# Tilt-Power.net
KiCad netlist of a schematic drawn in Altium Designer
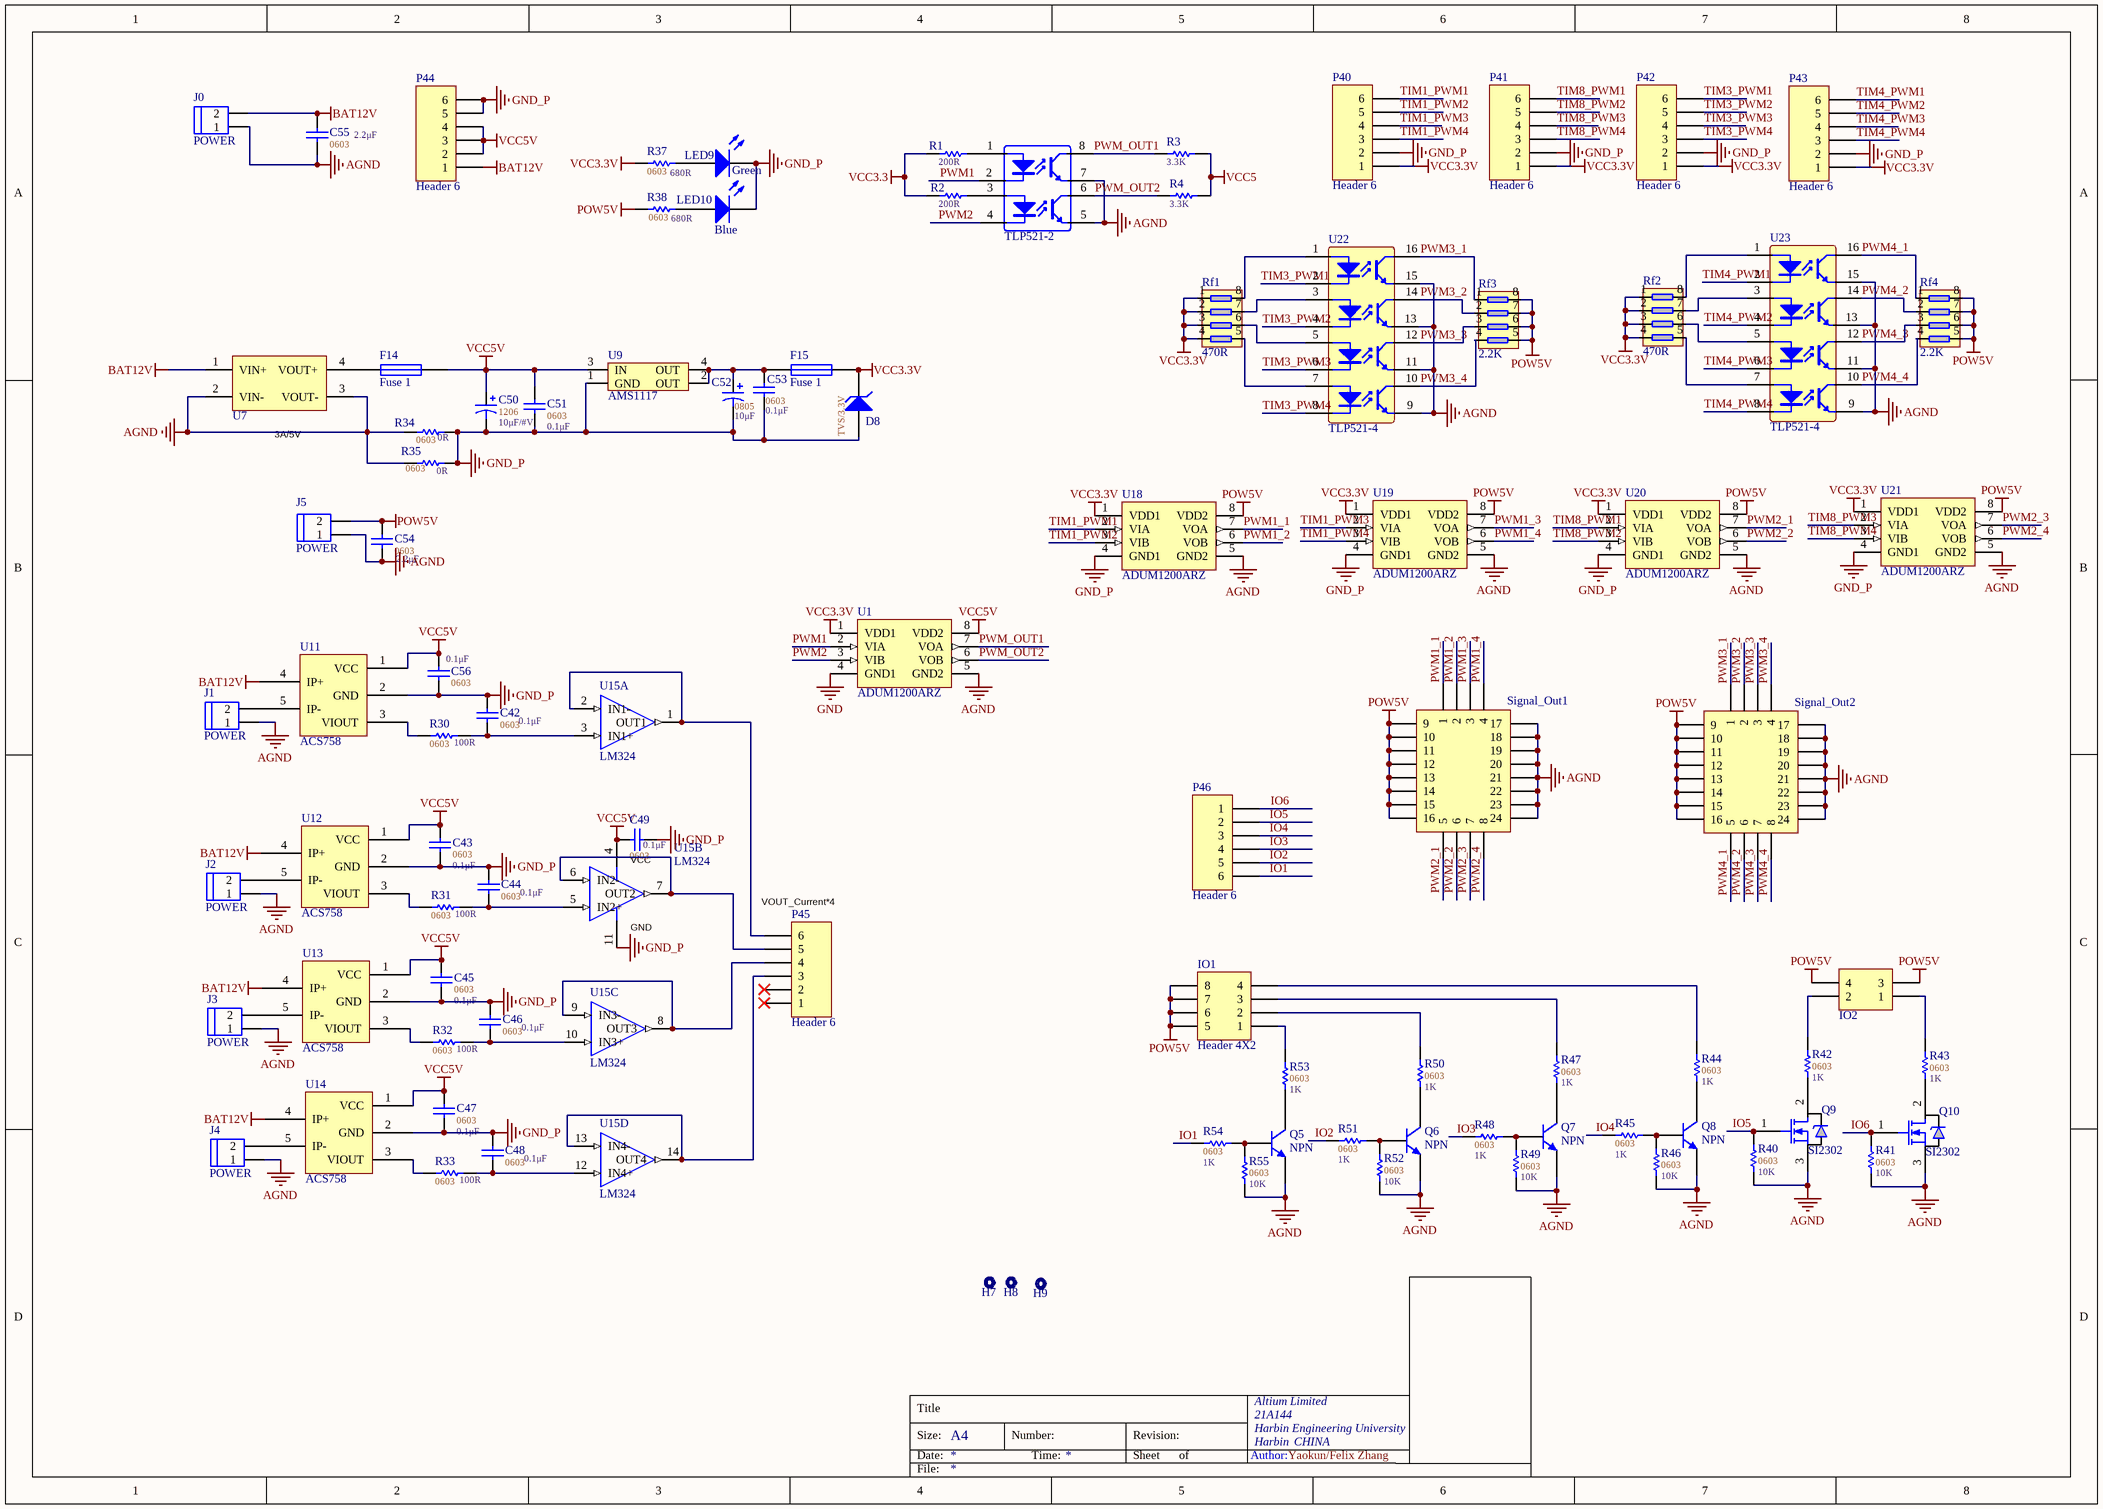
[diagram p0: Tilt-Power.SchDoc]

(export (version "E")
  (design (tool "Eeschema 10.0.6"))
  (components
    (comp (ref "*") (value "TLP521-2") (libsource (lib "Belong_to_Kongkong") (part "TLP521-2")))
    (comp (ref "C42")
      (value "0.1μF")
      (footprint "CAP_0603_16*08")
      (description "Capacitor")
      (fields (field (name "PACKAGEREFERENCE") "0603") (field (name "Comment") "0603"))
      (libsource (lib "Belong_to_Kongkong") (part "Cap"))
    )
    (comp (ref "C43")
      (value "0.1μF")
      (footprint "CAP_0603_16*08")
      (description "Capacitor")
      (fields (field (name "PACKAGEREFERENCE") "0603") (field (name "Comment") "0603"))
      (libsource (lib "Belong_to_Kongkong") (part "Cap"))
    )
    (comp (ref "C44")
      (value "0.1μF")
      (footprint "CAP_0603_16*08")
      (description "Capacitor")
      (fields (field (name "PACKAGEREFERENCE") "0603") (field (name "Comment") "0603"))
      (libsource (lib "Belong_to_Kongkong") (part "Cap"))
    )
    (comp (ref "C45")
      (value "0.1μF")
      (footprint "CAP_0603_16*08")
      (description "Capacitor")
      (fields (field (name "PACKAGEREFERENCE") "0603") (field (name "Comment") "0603"))
      (libsource (lib "Belong_to_Kongkong") (part "Cap"))
    )
    (comp (ref "C46")
      (value "0.1μF")
      (footprint "CAP_0603_16*08")
      (description "Capacitor")
      (fields (field (name "PACKAGEREFERENCE") "0603") (field (name "Comment") "0603"))
      (libsource (lib "Belong_to_Kongkong") (part "Cap"))
    )
    (comp (ref "C47")
      (value "0.1μF")
      (footprint "CAP_0603_16*08")
      (description "Capacitor")
      (fields (field (name "PACKAGEREFERENCE") "0603") (field (name "Comment") "0603"))
      (libsource (lib "Belong_to_Kongkong") (part "Cap"))
    )
    (comp (ref "C48")
      (value "0.1μF")
      (footprint "CAP_0603_16*08")
      (description "Capacitor")
      (fields (field (name "PACKAGEREFERENCE") "0603") (field (name "Comment") "0603"))
      (libsource (lib "Belong_to_Kongkong") (part "Cap"))
    )
    (comp (ref "C49")
      (value "0.1μF")
      (footprint "CAP_0603_16*08")
      (description "Capacitor")
      (fields (field (name "PACKAGEREFERENCE") "0603") (field (name "Comment") "0603"))
      (libsource (lib "Belong_to_Kongkong") (part "Cap"))
    )
    (comp (ref "C50")
      (value "10μF/#V")
      (footprint "CAP_1206")
      (description "Polarized Capacitor (Axial)")
      (fields (field (name "PACKAGEREFERENCE") "1206") (field (name "Comment") "Polar"))
      (libsource (lib "Belong_to_Kongkong") (part "Cap Pol"))
    )
    (comp (ref "C51")
      (value "0.1μF")
      (footprint "CAP_0603_16*08")
      (description "Capacitor")
      (fields (field (name "PACKAGEREFERENCE") "0603") (field (name "Comment") "0603"))
      (libsource (lib "Belong_to_Kongkong") (part "Cap"))
    )
    (comp (ref "C52")
      (value "10μF")
      (footprint "CAP_0805_20*12")
      (description "Polarized Capacitor (Axial)")
      (fields (field (name "PACKAGEREFERENCE") "0805") (field (name "Comment") "Polar"))
      (libsource (lib "Belong_to_Kongkong") (part "Cap Pol"))
    )
    (comp (ref "C53")
      (value "0.1μF")
      (footprint "CAP_0603_16*08")
      (description "Capacitor")
      (fields (field (name "PACKAGEREFERENCE") "0603") (field (name "Comment") "0603"))
      (libsource (lib "Belong_to_Kongkong") (part "Cap"))
    )
    (comp (ref "C54")
      (value "2.2μF")
      (footprint "CAP_0805_20*12")
      (description "Capacitor")
      (fields (field (name "PACKAGEREFERENCE") "0603") (field (name "Comment") "0603"))
      (libsource (lib "Belong_to_Kongkong") (part "Cap"))
    )
    (comp (ref "C55")
      (value "2.2μF")
      (footprint "CAP_0805_20*12")
      (description "Capacitor")
      (fields (field (name "PACKAGEREFERENCE") "0603") (field (name "Comment") "0603"))
      (libsource (lib "Belong_to_Kongkong") (part "Cap"))
    )
    (comp (ref "C56")
      (value "0.1μF")
      (footprint "CAP_0603_16*08")
      (description "Capacitor")
      (fields (field (name "PACKAGEREFERENCE") "0603") (field (name "Comment") "0603"))
      (libsource (lib "Belong_to_Kongkong") (part "Cap"))
    )
    (comp (ref "D8")
      (value "TVS/3.3V")
      (footprint "SOD523")
      (description "Zener Diode")
      (libsource (lib "Belong_to_Kongkong") (part "D Zener"))
    )
    (comp (ref "F14")
      (value "Fuse 1")
      (footprint "FUSE3.5*5.5")
      (description "Fuse")
      (libsource (lib "Belong_to_Kongkong") (part "Fuse 1"))
    )
    (comp (ref "F15")
      (value "Fuse 1")
      (footprint "RES_0805_20*12")
      (description "Fuse")
      (libsource (lib "Belong_to_Kongkong") (part "Fuse 1"))
    )
    (comp (ref "H7") (value "pad") (footprint "PAD_M2") (libsource (lib "Belong_to_Kongkong") (part "pad")))
    (comp (ref "H8") (value "pad") (footprint "PAD_M2") (libsource (lib "Belong_to_Kongkong") (part "pad")))
    (comp (ref "H9") (value "pad") (footprint "PAD_M2") (libsource (lib "Belong_to_Kongkong") (part "pad")))
    (comp (ref "IO1")
      (value "Header 4X2")
      (footprint "HEADER2*4_PIN")
      (description "Header, 4-Pin, Dual row")
      (libsource (lib "Belong_to_Kongkong") (part "Header 4X2"))
    )
    (comp (ref "IO2")
      (value "Header 2X2")
      (footprint "HEADER2*2_PIN")
      (description "Header, 2-Pin, Dual row")
      (libsource (lib "Belong_to_Kongkong") (part "Header 2X2"))
    )
    (comp (ref "J0")
      (value "POWER")
      (footprint "POWER_PADS")
      (libsource (lib "Belong_to_Kongkong") (part "HEAD2"))
    )
    (comp (ref "J1")
      (value "POWER")
      (footprint "POWER_PADS")
      (libsource (lib "Belong_to_Kongkong") (part "HEAD2"))
    )
    (comp (ref "J2")
      (value "POWER")
      (footprint "POWER_PADS")
      (libsource (lib "Belong_to_Kongkong") (part "HEAD2"))
    )
    (comp (ref "J3")
      (value "POWER")
      (footprint "POWER_PADS")
      (libsource (lib "Belong_to_Kongkong") (part "HEAD2"))
    )
    (comp (ref "J4")
      (value "POWER")
      (footprint "POWER_PADS")
      (libsource (lib "Belong_to_Kongkong") (part "HEAD2"))
    )
    (comp (ref "J5")
      (value "POWER")
      (footprint "POWER_PADS")
      (libsource (lib "Belong_to_Kongkong") (part "HEAD2"))
    )
    (comp (ref "LED9")
      (value "Green")
      (footprint "LED0603")
      (description "Typical RED, GREEN, YELLOW, AMBER GaAs LED")
      (libsource (lib "Belong_to_Kongkong") (part "LED"))
    )
    (comp (ref "LED10")
      (value "Blue")
      (footprint "LED0603")
      (description "Typical RED, GREEN, YELLOW, AMBER GaAs LED")
      (libsource (lib "Belong_to_Kongkong") (part "LED"))
    )
    (comp (ref "P40")
      (value "Header 6")
      (footprint "Modolex_6P")
      (description "Header, 6-Pin")
      (libsource (lib "Belong_to_Kongkong") (part "Header 6"))
    )
    (comp (ref "P41")
      (value "Header 6")
      (footprint "Modolex_6P")
      (description "Header, 6-Pin")
      (libsource (lib "Belong_to_Kongkong") (part "Header 6"))
    )
    (comp (ref "P42")
      (value "Header 6")
      (footprint "Modolex_6P")
      (description "Header, 6-Pin")
      (libsource (lib "Belong_to_Kongkong") (part "Header 6"))
    )
    (comp (ref "P43")
      (value "Header 6")
      (footprint "Modolex_6P")
      (description "Header, 6-Pin")
      (libsource (lib "Belong_to_Kongkong") (part "Header 6"))
    )
    (comp (ref "P44")
      (value "Header 6")
      (footprint "Modolex_6P")
      (description "Header, 6-Pin")
      (libsource (lib "Belong_to_Kongkong") (part "Header 6"))
    )
    (comp (ref "P45")
      (value "Header 6")
      (footprint "Modolex_6P")
      (description "Header, 6-Pin")
      (libsource (lib "") (part "Header 6_2"))
    )
    (comp (ref "P46")
      (value "Header 6")
      (footprint "Modolex_6P")
      (description "Header, 6-Pin")
      (libsource (lib "") (part "Header 6_1"))
    )
    (comp (ref "Q5")
      (value "NPN")
      (footprint "SOT23_J3Y")
      (description "NPN Bipolar Transistor")
      (libsource (lib "Belong_to_Kongkong") (part "NPN"))
    )
    (comp (ref "Q6")
      (value "NPN")
      (footprint "SOT23_J3Y")
      (description "NPN Bipolar Transistor")
      (libsource (lib "Belong_to_Kongkong") (part "NPN"))
    )
    (comp (ref "Q7")
      (value "NPN")
      (footprint "SOT23_J3Y")
      (description "NPN Bipolar Transistor")
      (libsource (lib "Belong_to_Kongkong") (part "NPN"))
    )
    (comp (ref "Q8")
      (value "NPN")
      (footprint "SOT23_J3Y")
      (description "NPN Bipolar Transistor")
      (libsource (lib "Belong_to_Kongkong") (part "NPN"))
    )
    (comp (ref "Q9")
      (value "SI2302")
      (footprint "SOT-23_MOSN")
      (description "N-Channel MOSFET")
      (libsource (lib "Belong_to_Kongkong") (part "MOSFET-N"))
    )
    (comp (ref "Q10")
      (value "SI2302")
      (footprint "SOT-23_MOSN")
      (description "N-Channel MOSFET")
      (libsource (lib "Belong_to_Kongkong") (part "MOSFET-N"))
    )
    (comp (ref "R1")
      (value "200R")
      (footprint "RES_0402_10*06")
      (description "Resistor")
      (fields (field (name "Comment") "SMD"))
      (libsource (lib "Belong_to_Kongkong") (part "RES_SMD"))
    )
    (comp (ref "R2")
      (value "200R")
      (footprint "RES_0402_10*06")
      (description "Resistor")
      (fields (field (name "Comment") "SMD"))
      (libsource (lib "Belong_to_Kongkong") (part "RES_SMD"))
    )
    (comp (ref "R3")
      (value "3.3K")
      (footprint "RES_0402_10*06")
      (description "Resistor")
      (fields (field (name "Comment") "SMD"))
      (libsource (lib "Belong_to_Kongkong") (part "RES_SMD"))
    )
    (comp (ref "R4")
      (value "3.3K")
      (footprint "RES_0402_10*06")
      (description "Resistor")
      (fields (field (name "Comment") "SMD"))
      (libsource (lib "Belong_to_Kongkong") (part "RES_SMD"))
    )
    (comp (ref "R30")
      (value "100R")
      (footprint "RES_0603_16*08")
      (description "Resistor")
      (fields (field (name "PACKAGEREFERENCE") "0603") (field (name "Comment") "SMD"))
      (libsource (lib "Belong_to_Kongkong") (part "RES_SMD"))
    )
    (comp (ref "R31")
      (value "100R")
      (footprint "RES_0603_16*08")
      (description "Resistor")
      (fields (field (name "PACKAGEREFERENCE") "0603") (field (name "Comment") "SMD"))
      (libsource (lib "Belong_to_Kongkong") (part "RES_SMD"))
    )
    (comp (ref "R32")
      (value "100R")
      (footprint "RES_0603_16*08")
      (description "Resistor")
      (fields (field (name "PACKAGEREFERENCE") "0603") (field (name "Comment") "SMD"))
      (libsource (lib "Belong_to_Kongkong") (part "RES_SMD"))
    )
    (comp (ref "R33")
      (value "100R")
      (footprint "RES_0603_16*08")
      (description "Resistor")
      (fields (field (name "PACKAGEREFERENCE") "0603") (field (name "Comment") "SMD"))
      (libsource (lib "Belong_to_Kongkong") (part "RES_SMD"))
    )
    (comp (ref "R34")
      (value "0R")
      (footprint "RES_1206")
      (description "Resistor")
      (fields (field (name "PACKAGEREFERENCE") "0603") (field (name "Comment") "SMD"))
      (libsource (lib "Belong_to_Kongkong") (part "RES_SMD"))
    )
    (comp (ref "R35")
      (value "0R")
      (footprint "RES_1206")
      (description "Resistor")
      (fields (field (name "PACKAGEREFERENCE") "0603") (field (name "Comment") "SMD"))
      (libsource (lib "Belong_to_Kongkong") (part "RES_SMD"))
    )
    (comp (ref "R37")
      (value "680R")
      (footprint "RES_0603_16*08")
      (description "Resistor")
      (fields (field (name "PACKAGEREFERENCE") "0603") (field (name "Comment") "SMD"))
      (libsource (lib "Belong_to_Kongkong") (part "RES_SMD"))
    )
    (comp (ref "R38")
      (value "680R")
      (footprint "RES_0603_16*08")
      (description "Resistor")
      (fields (field (name "PACKAGEREFERENCE") "0603") (field (name "Comment") "SMD"))
      (libsource (lib "Belong_to_Kongkong") (part "RES_SMD"))
    )
    (comp (ref "R40")
      (value "10K")
      (footprint "RES_0603_16*08")
      (description "Resistor")
      (fields (field (name "PACKAGEREFERENCE") "0603") (field (name "Comment") "SMD"))
      (libsource (lib "Belong_to_Kongkong") (part "RES_SMD"))
    )
    (comp (ref "R41")
      (value "10K")
      (footprint "RES_0603_16*08")
      (description "Resistor")
      (fields (field (name "PACKAGEREFERENCE") "0603") (field (name "Comment") "SMD"))
      (libsource (lib "Belong_to_Kongkong") (part "RES_SMD"))
    )
    (comp (ref "R42")
      (value "1K")
      (footprint "RES_0603_16*08")
      (description "Resistor")
      (fields (field (name "PACKAGEREFERENCE") "0603") (field (name "Comment") "SMD"))
      (libsource (lib "Belong_to_Kongkong") (part "RES_SMD"))
    )
    (comp (ref "R43")
      (value "1K")
      (footprint "RES_0603_16*08")
      (description "Resistor")
      (fields (field (name "PACKAGEREFERENCE") "0603") (field (name "Comment") "SMD"))
      (libsource (lib "Belong_to_Kongkong") (part "RES_SMD"))
    )
    (comp (ref "R44")
      (value "1K")
      (footprint "RES_0603_16*08")
      (description "Resistor")
      (fields (field (name "PACKAGEREFERENCE") "0603") (field (name "Comment") "SMD"))
      (libsource (lib "Belong_to_Kongkong") (part "RES_SMD"))
    )
    (comp (ref "R45")
      (value "1K")
      (footprint "RES_0603_16*08")
      (description "Resistor")
      (fields (field (name "PACKAGEREFERENCE") "0603") (field (name "Comment") "SMD"))
      (libsource (lib "Belong_to_Kongkong") (part "RES_SMD"))
    )
    (comp (ref "R46")
      (value "10K")
      (footprint "RES_0603_16*08")
      (description "Resistor")
      (fields (field (name "PACKAGEREFERENCE") "0603") (field (name "Comment") "SMD"))
      (libsource (lib "Belong_to_Kongkong") (part "RES_SMD"))
    )
    (comp (ref "R47")
      (value "1K")
      (footprint "RES_0603_16*08")
      (description "Resistor")
      (fields (field (name "PACKAGEREFERENCE") "0603") (field (name "Comment") "SMD"))
      (libsource (lib "Belong_to_Kongkong") (part "RES_SMD"))
    )
    (comp (ref "R48")
      (value "1K")
      (footprint "RES_0603_16*08")
      (description "Resistor")
      (fields (field (name "PACKAGEREFERENCE") "0603") (field (name "Comment") "SMD"))
      (libsource (lib "Belong_to_Kongkong") (part "RES_SMD"))
    )
    (comp (ref "R49")
      (value "10K")
      (footprint "RES_0603_16*08")
      (description "Resistor")
      (fields (field (name "PACKAGEREFERENCE") "0603") (field (name "Comment") "SMD"))
      (libsource (lib "Belong_to_Kongkong") (part "RES_SMD"))
    )
    (comp (ref "R50")
      (value "1K")
      (footprint "RES_0603_16*08")
      (description "Resistor")
      (fields (field (name "PACKAGEREFERENCE") "0603") (field (name "Comment") "SMD"))
      (libsource (lib "Belong_to_Kongkong") (part "RES_SMD"))
    )
    (comp (ref "R51")
      (value "1K")
      (footprint "RES_0603_16*08")
      (description "Resistor")
      (fields (field (name "PACKAGEREFERENCE") "0603") (field (name "Comment") "SMD"))
      (libsource (lib "Belong_to_Kongkong") (part "RES_SMD"))
    )
    (comp (ref "R52")
      (value "10K")
      (footprint "RES_0603_16*08")
      (description "Resistor")
      (fields (field (name "PACKAGEREFERENCE") "0603") (field (name "Comment") "SMD"))
      (libsource (lib "Belong_to_Kongkong") (part "RES_SMD"))
    )
    (comp (ref "R53")
      (value "1K")
      (footprint "RES_0603_16*08")
      (description "Resistor")
      (fields (field (name "PACKAGEREFERENCE") "0603") (field (name "Comment") "SMD"))
      (libsource (lib "Belong_to_Kongkong") (part "RES_SMD"))
    )
    (comp (ref "R54")
      (value "1K")
      (footprint "RES_0603_16*08")
      (description "Resistor")
      (fields (field (name "PACKAGEREFERENCE") "0603") (field (name "Comment") "SMD"))
      (libsource (lib "Belong_to_Kongkong") (part "RES_SMD"))
    )
    (comp (ref "R55")
      (value "10K")
      (footprint "RES_0603_16*08")
      (description "Resistor")
      (fields (field (name "PACKAGEREFERENCE") "0603") (field (name "Comment") "SMD"))
      (libsource (lib "Belong_to_Kongkong") (part "RES_SMD"))
    )
    (comp (ref "Rf1")
      (value "470R")
      (footprint "RES_FOUR_0603")
      (libsource (lib "Belong_to_Kongkong") (part "RES_4P"))
    )
    (comp (ref "Rf2")
      (value "470R")
      (footprint "RES_FOUR_0603")
      (libsource (lib "Belong_to_Kongkong") (part "RES_4P"))
    )
    (comp (ref "Rf3")
      (value "2.2K")
      (footprint "RES_FOUR_0603")
      (libsource (lib "Belong_to_Kongkong") (part "RES_4P"))
    )
    (comp (ref "Rf4")
      (value "2.2K")
      (footprint "RES_FOUR_0603")
      (libsource (lib "Belong_to_Kongkong") (part "RES_4P"))
    )
    (comp (ref "Signal_Out1")
      (value "PWM")
      (footprint "HEADER3*8")
      (libsource (lib "Belong_to_Kongkong") (part "HEADER8*3"))
    )
    (comp (ref "Signal_Out2")
      (value "PWM")
      (footprint "HEADER3*8")
      (libsource (lib "Belong_to_Kongkong") (part "HEADER8*3"))
    )
    (comp (ref "U1")
      (value "ADUM1200ARZ")
      (footprint "SOIC-8")
      (description "ADUM1200")
      (libsource (lib "Belong_to_Kongkong") (part "ADUM1200ARZ"))
    )
    (comp (ref "U7")
      (value "Voltage_Trans_Moduel")
      (footprint "3A_Moduel")
      (libsource (lib "Belong_to_Kongkong") (part "Voltage_Trans_Moduel"))
    )
    (comp (ref "U9")
      (value "AMS1117")
      (footprint "SOT223_M")
      (libsource (lib "Belong_to_Kongkong") (part "AMS1117"))
    )
    (comp (ref "U11")
      (value "ACS758")
      (footprint "ACS758")
      (libsource (lib "Belong_to_Kongkong") (part "ACS758"))
    )
    (comp (ref "U12")
      (value "ACS758")
      (footprint "ACS758")
      (libsource (lib "Belong_to_Kongkong") (part "ACS758"))
    )
    (comp (ref "U13")
      (value "ACS758")
      (footprint "ACS758")
      (libsource (lib "Belong_to_Kongkong") (part "ACS758"))
    )
    (comp (ref "U14")
      (value "ACS758")
      (footprint "ACS758")
      (libsource (lib "Belong_to_Kongkong") (part "ACS758"))
    )
    (comp (ref "U15")
      (value "LM324")
      (footprint "SOP-14N")
      (libsource (lib "Belong_to_Kongkong") (part "LM324"))
    )
    (comp (ref "U18")
      (value "ADUM1200ARZ")
      (footprint "SOIC-8")
      (description "ADUM1200")
      (libsource (lib "Belong_to_Kongkong") (part "ADUM1200ARZ"))
    )
    (comp (ref "U19")
      (value "ADUM1200ARZ")
      (footprint "SOIC-8")
      (description "ADUM1200")
      (libsource (lib "Belong_to_Kongkong") (part "ADUM1200ARZ"))
    )
    (comp (ref "U20")
      (value "ADUM1200ARZ")
      (footprint "SOIC-8")
      (description "ADUM1200")
      (libsource (lib "Belong_to_Kongkong") (part "ADUM1200ARZ"))
    )
    (comp (ref "U21")
      (value "ADUM1200ARZ")
      (footprint "SOIC-8")
      (description "ADUM1200")
      (libsource (lib "Belong_to_Kongkong") (part "ADUM1200ARZ"))
    )
    (comp (ref "U22")
      (value "TLP521-4")
      (footprint "SOP16")
      (libsource (lib "Belong_to_Kongkong") (part "TLP521-4"))
    )
    (comp (ref "U23")
      (value "TLP521-4")
      (footprint "SOP16")
      (libsource (lib "Belong_to_Kongkong") (part "TLP521-4"))
    )
  )
  (nets
    (net (code "1") (name "/IO1") (class "Default")
      (node (ref "P46") (pin "6") (pinfunction "6_6") (pintype "passive"))
      (node (ref "R54") (pin "1") (pinfunction "1_1") (pintype "passive"))
    )
    (net (code "2") (name "/IO2") (class "Default")
      (node (ref "P46") (pin "5") (pinfunction "5_5") (pintype "passive"))
      (node (ref "R51") (pin "1") (pinfunction "1_1") (pintype "passive"))
    )
    (net (code "3") (name "/IO3") (class "Default")
      (node (ref "P46") (pin "4") (pinfunction "4_4") (pintype "passive"))
      (node (ref "R48") (pin "1") (pinfunction "1_1") (pintype "passive"))
    )
    (net (code "4") (name "/IO4") (class "Default")
      (node (ref "P46") (pin "3") (pinfunction "3_3") (pintype "passive"))
      (node (ref "R45") (pin "1") (pinfunction "1_1") (pintype "passive"))
    )
    (net (code "5") (name "/IO5") (class "Default")
      (node (ref "P46") (pin "2") (pinfunction "2_2") (pintype "passive"))
      (node (ref "Q9") (pin "1") (pinfunction "G_1") (pintype "passive"))
      (node (ref "R40") (pin "2") (pinfunction "2_2") (pintype "passive"))
    )
    (net (code "6") (name "/IO6") (class "Default")
      (node (ref "P46") (pin "1") (pinfunction "1_1") (pintype "passive"))
      (node (ref "Q10") (pin "1") (pinfunction "G_1") (pintype "passive"))
      (node (ref "R41") (pin "2") (pinfunction "2_2") (pintype "passive"))
    )
    (net (code "7") (name "/PWM1") (class "Default")
      (node (ref "*") (pin "2") (pinfunction "2_2") (pintype "power_in"))
      (node (ref "U1") (pin "2") (pinfunction "VIA_2") (pintype "input"))
    )
    (net (code "8") (name "/PWM1_1") (class "Default")
      (node (ref "Signal_Out1") (pin "1") (pinfunction "1_1") (pintype "passive"))
      (node (ref "U18") (pin "7") (pinfunction "VOA_7") (pintype "output"))
    )
    (net (code "9") (name "/PWM1_2") (class "Default")
      (node (ref "Signal_Out1") (pin "2") (pinfunction "2_2") (pintype "passive"))
      (node (ref "U18") (pin "6") (pinfunction "VOB_6") (pintype "output"))
    )
    (net (code "10") (name "/PWM1_3") (class "Default")
      (node (ref "Signal_Out1") (pin "3") (pinfunction "3_3") (pintype "passive"))
      (node (ref "U19") (pin "7") (pinfunction "VOA_7") (pintype "output"))
    )
    (net (code "11") (name "/PWM1_4") (class "Default")
      (node (ref "Signal_Out1") (pin "4") (pinfunction "4_4") (pintype "passive"))
      (node (ref "U19") (pin "6") (pinfunction "VOB_6") (pintype "output"))
    )
    (net (code "12") (name "/PWM2") (class "Default")
      (node (ref "*") (pin "4") (pinfunction "4_4") (pintype "power_in"))
      (node (ref "U1") (pin "3") (pinfunction "VIB_3") (pintype "input"))
    )
    (net (code "13") (name "/PWM2_1") (class "Default")
      (node (ref "Signal_Out1") (pin "5") (pinfunction "5_5") (pintype "passive"))
      (node (ref "U20") (pin "7") (pinfunction "VOA_7") (pintype "output"))
    )
    (net (code "14") (name "/PWM2_2") (class "Default")
      (node (ref "Signal_Out1") (pin "6") (pinfunction "6_6") (pintype "passive"))
      (node (ref "U20") (pin "6") (pinfunction "VOB_6") (pintype "output"))
    )
    (net (code "15") (name "/PWM2_3") (class "Default")
      (node (ref "Signal_Out1") (pin "7") (pinfunction "7_7") (pintype "passive"))
      (node (ref "U21") (pin "7") (pinfunction "VOA_7") (pintype "output"))
    )
    (net (code "16") (name "/PWM2_4") (class "Default")
      (node (ref "Signal_Out1") (pin "8") (pinfunction "8_8") (pintype "passive"))
      (node (ref "U21") (pin "6") (pinfunction "VOB_6") (pintype "output"))
    )
    (net (code "17") (name "/PWM3_1") (class "Default")
      (node (ref "Rf3") (pin "1") (pinfunction "1_1") (pintype "passive"))
      (node (ref "Signal_Out2") (pin "1") (pinfunction "1_1") (pintype "passive"))
      (node (ref "U22") (pin "16") (pinfunction "16_16") (pintype "power_in"))
    )
    (net (code "18") (name "/PWM3_2") (class "Default")
      (node (ref "Rf3") (pin "2") (pinfunction "2_2") (pintype "passive"))
      (node (ref "Signal_Out2") (pin "2") (pinfunction "2_2") (pintype "passive"))
      (node (ref "U22") (pin "14") (pinfunction "14_14") (pintype "power_in"))
    )
    (net (code "19") (name "/PWM3_3") (class "Default")
      (node (ref "Rf3") (pin "3") (pinfunction "3_3") (pintype "passive"))
      (node (ref "Signal_Out2") (pin "3") (pinfunction "3_3") (pintype "passive"))
      (node (ref "U22") (pin "12") (pinfunction "12_12") (pintype "power_in"))
    )
    (net (code "20") (name "/PWM3_4") (class "Default")
      (node (ref "Rf3") (pin "4") (pinfunction "4_4") (pintype "passive"))
      (node (ref "Signal_Out2") (pin "4") (pinfunction "4_4") (pintype "passive"))
      (node (ref "U22") (pin "10") (pinfunction "10_10") (pintype "power_in"))
    )
    (net (code "21") (name "/PWM4_1") (class "Default")
      (node (ref "Rf4") (pin "1") (pinfunction "1_1") (pintype "passive"))
      (node (ref "Signal_Out2") (pin "5") (pinfunction "5_5") (pintype "passive"))
      (node (ref "U23") (pin "16") (pinfunction "16_16") (pintype "power_in"))
    )
    (net (code "22") (name "/PWM4_2") (class "Default")
      (node (ref "Rf4") (pin "2") (pinfunction "2_2") (pintype "passive"))
      (node (ref "Signal_Out2") (pin "6") (pinfunction "6_6") (pintype "passive"))
      (node (ref "U23") (pin "14") (pinfunction "14_14") (pintype "power_in"))
    )
    (net (code "23") (name "/PWM4_3") (class "Default")
      (node (ref "Rf4") (pin "3") (pinfunction "3_3") (pintype "passive"))
      (node (ref "Signal_Out2") (pin "7") (pinfunction "7_7") (pintype "passive"))
      (node (ref "U23") (pin "12") (pinfunction "12_12") (pintype "power_in"))
    )
    (net (code "24") (name "/PWM4_4") (class "Default")
      (node (ref "Rf4") (pin "4") (pinfunction "4_4") (pintype "passive"))
      (node (ref "Signal_Out2") (pin "8") (pinfunction "8_8") (pintype "passive"))
      (node (ref "U23") (pin "10") (pinfunction "10_10") (pintype "power_in"))
    )
    (net (code "25") (name "/PWM_OUT1") (class "Default")
      (node (ref "*") (pin "8") (pinfunction "8_8") (pintype "power_in"))
      (node (ref "R3") (pin "1") (pinfunction "1_1") (pintype "passive"))
      (node (ref "U1") (pin "7") (pinfunction "VOA_7") (pintype "output"))
    )
    (net (code "26") (name "/PWM_OUT2") (class "Default")
      (node (ref "*") (pin "6") (pinfunction "6_6") (pintype "power_in"))
      (node (ref "R4") (pin "1") (pinfunction "1_1") (pintype "passive"))
      (node (ref "U1") (pin "6") (pinfunction "VOB_6") (pintype "output"))
    )
    (net (code "27") (name "/TIM1_PWM1") (class "Default")
      (node (ref "P40") (pin "6") (pinfunction "6_6") (pintype "passive"))
      (node (ref "U18") (pin "2") (pinfunction "VIA_2") (pintype "input"))
    )
    (net (code "28") (name "/TIM1_PWM2") (class "Default")
      (node (ref "P40") (pin "5") (pinfunction "5_5") (pintype "passive"))
      (node (ref "U18") (pin "3") (pinfunction "VIB_3") (pintype "input"))
    )
    (net (code "29") (name "/TIM1_PWM3") (class "Default")
      (node (ref "P40") (pin "4") (pinfunction "4_4") (pintype "passive"))
      (node (ref "U19") (pin "2") (pinfunction "VIA_2") (pintype "input"))
    )
    (net (code "30") (name "/TIM1_PWM4") (class "Default")
      (node (ref "P40") (pin "3") (pinfunction "3_3") (pintype "passive"))
      (node (ref "U19") (pin "3") (pinfunction "VIB_3") (pintype "input"))
    )
    (net (code "31") (name "/TIM3_PWM1") (class "Default")
      (node (ref "P42") (pin "6") (pinfunction "6_6") (pintype "passive"))
      (node (ref "U22") (pin "2") (pinfunction "2_2") (pintype "power_in"))
    )
    (net (code "32") (name "/TIM3_PWM2") (class "Default")
      (node (ref "P42") (pin "5") (pinfunction "5_5") (pintype "passive"))
      (node (ref "U22") (pin "4") (pinfunction "4_4") (pintype "power_in"))
    )
    (net (code "33") (name "/TIM3_PWM3") (class "Default")
      (node (ref "P42") (pin "4") (pinfunction "4_4") (pintype "passive"))
      (node (ref "U22") (pin "6") (pinfunction "6_6") (pintype "power_in"))
    )
    (net (code "34") (name "/TIM3_PWM4") (class "Default")
      (node (ref "P42") (pin "3") (pinfunction "3_3") (pintype "passive"))
      (node (ref "U22") (pin "8") (pinfunction "8_8") (pintype "power_in"))
    )
    (net (code "35") (name "/TIM4_PWM1") (class "Default")
      (node (ref "P43") (pin "6") (pinfunction "6_6") (pintype "passive"))
      (node (ref "U23") (pin "2") (pinfunction "2_2") (pintype "power_in"))
    )
    (net (code "36") (name "/TIM4_PWM2") (class "Default")
      (node (ref "P43") (pin "5") (pinfunction "5_5") (pintype "passive"))
      (node (ref "U23") (pin "4") (pinfunction "4_4") (pintype "power_in"))
    )
    (net (code "37") (name "/TIM4_PWM3") (class "Default")
      (node (ref "P43") (pin "4") (pinfunction "4_4") (pintype "passive"))
      (node (ref "U23") (pin "6") (pinfunction "6_6") (pintype "power_in"))
    )
    (net (code "38") (name "/TIM4_PWM4") (class "Default")
      (node (ref "P43") (pin "3") (pinfunction "3_3") (pintype "passive"))
      (node (ref "U23") (pin "8") (pinfunction "8_8") (pintype "power_in"))
    )
    (net (code "39") (name "/TIM8_PWM1") (class "Default")
      (node (ref "P41") (pin "6") (pinfunction "6_6") (pintype "passive"))
      (node (ref "U20") (pin "2") (pinfunction "VIA_2") (pintype "input"))
    )
    (net (code "40") (name "/TIM8_PWM2") (class "Default")
      (node (ref "P41") (pin "5") (pinfunction "5_5") (pintype "passive"))
      (node (ref "U20") (pin "3") (pinfunction "VIB_3") (pintype "input"))
    )
    (net (code "41") (name "/TIM8_PWM3") (class "Default")
      (node (ref "P41") (pin "4") (pinfunction "4_4") (pintype "passive"))
      (node (ref "U21") (pin "2") (pinfunction "VIA_2") (pintype "input"))
    )
    (net (code "42") (name "/TIM8_PWM4") (class "Default")
      (node (ref "P41") (pin "3") (pinfunction "3_3") (pintype "passive"))
      (node (ref "U21") (pin "3") (pinfunction "VIB_3") (pintype "input"))
    )
    (net (code "43") (name "AGND") (class "Default")
      (node (ref "*") (pin "5") (pinfunction "5_5") (pintype "power_in"))
      (node (ref "*") (pin "7") (pinfunction "7_7") (pintype "power_in"))
      (node (ref "C54") (pin "1") (pinfunction "1_1") (pintype "passive"))
      (node (ref "C55") (pin "1") (pinfunction "1_1") (pintype "passive"))
      (node (ref "J0") (pin "1") (pinfunction "1_1") (pintype "passive"))
      (node (ref "J1") (pin "1") (pinfunction "1_1") (pintype "passive"))
      (node (ref "J2") (pin "1") (pinfunction "1_1") (pintype "passive"))
      (node (ref "J3") (pin "1") (pinfunction "1_1") (pintype "passive"))
      (node (ref "J4") (pin "1") (pinfunction "1_1") (pintype "passive"))
      (node (ref "J5") (pin "1") (pinfunction "1_1") (pintype "passive"))
      (node (ref "Q10") (pin "3") (pinfunction "S_3") (pintype "passive"))
      (node (ref "Q5") (pin "3") (pinfunction "E_3") (pintype "passive"))
      (node (ref "Q6") (pin "3") (pinfunction "E_3") (pintype "passive"))
      (node (ref "Q7") (pin "3") (pinfunction "E_3") (pintype "passive"))
      (node (ref "Q8") (pin "3") (pinfunction "E_3") (pintype "passive"))
      (node (ref "Q9") (pin "3") (pinfunction "S_3") (pintype "passive"))
      (node (ref "R34") (pin "1") (pinfunction "1_1") (pintype "passive"))
      (node (ref "R35") (pin "1") (pinfunction "1_1") (pintype "passive"))
      (node (ref "R40") (pin "1") (pinfunction "1_1") (pintype "passive"))
      (node (ref "R41") (pin "1") (pinfunction "1_1") (pintype "passive"))
      (node (ref "R46") (pin "1") (pinfunction "1_1") (pintype "passive"))
      (node (ref "R49") (pin "1") (pinfunction "1_1") (pintype "passive"))
      (node (ref "R52") (pin "1") (pinfunction "1_1") (pintype "passive"))
      (node (ref "R55") (pin "1") (pinfunction "1_1") (pintype "passive"))
      (node (ref "Signal_Out1") (pin "17") (pinfunction "17_17") (pintype "passive"))
      (node (ref "Signal_Out1") (pin "18") (pinfunction "18_18") (pintype "passive"))
      (node (ref "Signal_Out1") (pin "19") (pinfunction "19_19") (pintype "passive"))
      (node (ref "Signal_Out1") (pin "20") (pinfunction "20_20") (pintype "passive"))
      (node (ref "Signal_Out1") (pin "21") (pinfunction "21_21") (pintype "passive"))
      (node (ref "Signal_Out1") (pin "22") (pinfunction "22_22") (pintype "passive"))
      (node (ref "Signal_Out1") (pin "23") (pinfunction "23_23") (pintype "passive"))
      (node (ref "Signal_Out1") (pin "24") (pinfunction "24_24") (pintype "passive"))
      (node (ref "Signal_Out2") (pin "17") (pinfunction "17_17") (pintype "passive"))
      (node (ref "Signal_Out2") (pin "18") (pinfunction "18_18") (pintype "passive"))
      (node (ref "Signal_Out2") (pin "19") (pinfunction "19_19") (pintype "passive"))
      (node (ref "Signal_Out2") (pin "20") (pinfunction "20_20") (pintype "passive"))
      (node (ref "Signal_Out2") (pin "21") (pinfunction "21_21") (pintype "passive"))
      (node (ref "Signal_Out2") (pin "22") (pinfunction "22_22") (pintype "passive"))
      (node (ref "Signal_Out2") (pin "23") (pinfunction "23_23") (pintype "passive"))
      (node (ref "Signal_Out2") (pin "24") (pinfunction "24_24") (pintype "passive"))
      (node (ref "U1") (pin "5") (pinfunction "GND2_5") (pintype "power_in"))
      (node (ref "U18") (pin "5") (pinfunction "GND2_5") (pintype "power_in"))
      (node (ref "U19") (pin "5") (pinfunction "GND2_5") (pintype "power_in"))
      (node (ref "U20") (pin "5") (pinfunction "GND2_5") (pintype "power_in"))
      (node (ref "U21") (pin "5") (pinfunction "GND2_5") (pintype "power_in"))
      (node (ref "U22") (pin "11") (pinfunction "11_11") (pintype "power_in"))
      (node (ref "U22") (pin "13") (pinfunction "13_13") (pintype "power_in"))
      (node (ref "U22") (pin "15") (pinfunction "15_15") (pintype "power_in"))
      (node (ref "U22") (pin "9") (pinfunction "9_9") (pintype "power_in"))
      (node (ref "U23") (pin "11") (pinfunction "11_11") (pintype "power_in"))
      (node (ref "U23") (pin "13") (pinfunction "13_13") (pintype "power_in"))
      (node (ref "U23") (pin "15") (pinfunction "15_15") (pintype "power_in"))
      (node (ref "U23") (pin "9") (pinfunction "9_9") (pintype "power_in"))
      (node (ref "U7") (pin "2") (pinfunction "VIN-_2") (pintype "power_in"))
      (node (ref "U7") (pin "3") (pinfunction "VOUT-_3") (pintype "power_in"))
    )
    (net (code "44") (name "BAT12V") (class "Default")
      (node (ref "C55") (pin "2") (pinfunction "2_2") (pintype "passive"))
      (node (ref "J0") (pin "2") (pinfunction "2_2") (pintype "passive"))
      (node (ref "P44") (pin "1") (pinfunction "1_1") (pintype "passive"))
      (node (ref "U11") (pin "4") (pinfunction "IP+_4") (pintype "passive"))
      (node (ref "U12") (pin "4") (pinfunction "IP+_4") (pintype "passive"))
      (node (ref "U13") (pin "4") (pinfunction "IP+_4") (pintype "passive"))
      (node (ref "U14") (pin "4") (pinfunction "IP+_4") (pintype "passive"))
      (node (ref "U7") (pin "1") (pinfunction "VIN+_1") (pintype "power_in"))
    )
    (net (code "45") (name "GND") (class "Default")
      (node (ref "U1") (pin "4") (pinfunction "GND1_4") (pintype "power_in"))
    )
    (net (code "46") (name "GND_P") (class "Default")
      (node (ref "C42") (pin "2") (pinfunction "2_2") (pintype "passive"))
      (node (ref "C43") (pin "1") (pinfunction "1_1") (pintype "passive"))
      (node (ref "C44") (pin "2") (pinfunction "2_2") (pintype "passive"))
      (node (ref "C45") (pin "1") (pinfunction "1_1") (pintype "passive"))
      (node (ref "C46") (pin "2") (pinfunction "2_2") (pintype "passive"))
      (node (ref "C47") (pin "1") (pinfunction "1_1") (pintype "passive"))
      (node (ref "C48") (pin "2") (pinfunction "2_2") (pintype "passive"))
      (node (ref "C49") (pin "1") (pinfunction "1_1") (pintype "passive"))
      (node (ref "C50") (pin "2") (pinfunction "2_2") (pintype "passive"))
      (node (ref "C51") (pin "1") (pinfunction "1_1") (pintype "passive"))
      (node (ref "C52") (pin "2") (pinfunction "2_2") (pintype "passive"))
      (node (ref "C53") (pin "1") (pinfunction "1_1") (pintype "passive"))
      (node (ref "C56") (pin "1") (pinfunction "1_1") (pintype "passive"))
      (node (ref "D8") (pin "1") (pinfunction "A_1") (pintype "passive"))
      (node (ref "LED10") (pin "2") (pinfunction "K_2") (pintype "passive"))
      (node (ref "LED9") (pin "2") (pinfunction "K_2") (pintype "passive"))
      (node (ref "P40") (pin "2") (pinfunction "2_2") (pintype "passive"))
      (node (ref "P41") (pin "2") (pinfunction "2_2") (pintype "passive"))
      (node (ref "P42") (pin "2") (pinfunction "2_2") (pintype "passive"))
      (node (ref "P43") (pin "2") (pinfunction "2_2") (pintype "passive"))
      (node (ref "P44") (pin "5") (pinfunction "5_5") (pintype "passive"))
      (node (ref "P44") (pin "6") (pinfunction "6_6") (pintype "passive"))
      (node (ref "R34") (pin "2") (pinfunction "2_2") (pintype "passive"))
      (node (ref "R35") (pin "2") (pinfunction "2_2") (pintype "passive"))
      (node (ref "U11") (pin "2") (pinfunction "GND_2") (pintype "passive"))
      (node (ref "U12") (pin "2") (pinfunction "GND_2") (pintype "passive"))
      (node (ref "U13") (pin "2") (pinfunction "GND_2") (pintype "passive"))
      (node (ref "U14") (pin "2") (pinfunction "GND_2") (pintype "passive"))
      (node (ref "U15") (pin "11") (pinfunction "GND_11") (pintype "power_in"))
      (node (ref "U18") (pin "4") (pinfunction "GND1_4") (pintype "power_in"))
      (node (ref "U19") (pin "4") (pinfunction "GND1_4") (pintype "power_in"))
      (node (ref "U20") (pin "4") (pinfunction "GND1_4") (pintype "power_in"))
      (node (ref "U21") (pin "4") (pinfunction "GND1_4") (pintype "power_in"))
      (node (ref "U9") (pin "1") (pinfunction "GND_1") (pintype "passive"))
    )
    (net (code "47") (name "Net-(*-Pad1)") (class "Default")
      (node (ref "*") (pin "1") (pinfunction "1_1") (pintype "power_in"))
      (node (ref "R1") (pin "2") (pinfunction "2_2") (pintype "passive"))
    )
    (net (code "48") (name "Net-(*-Pad3)") (class "Default")
      (node (ref "*") (pin "3") (pinfunction "3_3") (pintype "power_in"))
      (node (ref "R2") (pin "2") (pinfunction "2_2") (pintype "passive"))
    )
    (net (code "49") (name "Net-(C52-Pad1)") (class "Default")
      (node (ref "C52") (pin "1") (pinfunction "1_1") (pintype "passive"))
      (node (ref "C53") (pin "2") (pinfunction "2_2") (pintype "passive"))
      (node (ref "F15") (pin "1") (pinfunction "1_1") (pintype "passive"))
      (node (ref "U9") (pin "2") (pinfunction "OUT_2") (pintype "passive"))
      (node (ref "U9") (pin "4") (pinfunction "OUT_4") (pintype "passive"))
    )
    (net (code "50") (name "Net-(IO1-Pad1)") (class "Default")
      (node (ref "IO1") (pin "1") (pinfunction "1_1") (pintype "passive"))
      (node (ref "R53") (pin "2") (pinfunction "2_2") (pintype "passive"))
    )
    (net (code "51") (name "Net-(IO1-Pad2)") (class "Default")
      (node (ref "IO1") (pin "2") (pinfunction "2_2") (pintype "passive"))
      (node (ref "R50") (pin "2") (pinfunction "2_2") (pintype "passive"))
    )
    (net (code "52") (name "Net-(IO1-Pad3)") (class "Default")
      (node (ref "IO1") (pin "3") (pinfunction "3_3") (pintype "passive"))
      (node (ref "R47") (pin "2") (pinfunction "2_2") (pintype "passive"))
    )
    (net (code "53") (name "Net-(IO1-Pad4)") (class "Default")
      (node (ref "IO1") (pin "4") (pinfunction "4_4") (pintype "passive"))
      (node (ref "R44") (pin "2") (pinfunction "2_2") (pintype "passive"))
    )
    (net (code "54") (name "Net-(IO2-Pad1)") (class "Default")
      (node (ref "IO2") (pin "1") (pinfunction "1_1") (pintype "passive"))
      (node (ref "R43") (pin "2") (pinfunction "2_2") (pintype "passive"))
    )
    (net (code "55") (name "Net-(IO2-Pad2)") (class "Default")
      (node (ref "IO2") (pin "2") (pinfunction "2_2") (pintype "passive"))
      (node (ref "R42") (pin "2") (pinfunction "2_2") (pintype "passive"))
    )
    (net (code "56") (name "Net-(LED9-A)") (class "Default")
      (node (ref "LED9") (pin "1") (pinfunction "A_1") (pintype "passive"))
      (node (ref "R37") (pin "2") (pinfunction "2_2") (pintype "passive"))
    )
    (net (code "57") (name "Net-(LED10-A)") (class "Default")
      (node (ref "LED10") (pin "1") (pinfunction "A_1") (pintype "passive"))
      (node (ref "R38") (pin "2") (pinfunction "2_2") (pintype "passive"))
    )
    (net (code "58") (name "Net-(Q5-B)") (class "Default")
      (node (ref "Q5") (pin "2") (pinfunction "B_2") (pintype "passive"))
      (node (ref "R54") (pin "2") (pinfunction "2_2") (pintype "passive"))
      (node (ref "R55") (pin "2") (pinfunction "2_2") (pintype "passive"))
    )
    (net (code "59") (name "Net-(Q5-C)") (class "Default")
      (node (ref "Q5") (pin "1") (pinfunction "C_1") (pintype "passive"))
      (node (ref "R53") (pin "1") (pinfunction "1_1") (pintype "passive"))
    )
    (net (code "60") (name "Net-(Q6-B)") (class "Default")
      (node (ref "Q6") (pin "2") (pinfunction "B_2") (pintype "passive"))
      (node (ref "R51") (pin "2") (pinfunction "2_2") (pintype "passive"))
      (node (ref "R52") (pin "2") (pinfunction "2_2") (pintype "passive"))
    )
    (net (code "61") (name "Net-(Q6-C)") (class "Default")
      (node (ref "Q6") (pin "1") (pinfunction "C_1") (pintype "passive"))
      (node (ref "R50") (pin "1") (pinfunction "1_1") (pintype "passive"))
    )
    (net (code "62") (name "Net-(Q7-B)") (class "Default")
      (node (ref "Q7") (pin "2") (pinfunction "B_2") (pintype "passive"))
      (node (ref "R48") (pin "2") (pinfunction "2_2") (pintype "passive"))
      (node (ref "R49") (pin "2") (pinfunction "2_2") (pintype "passive"))
    )
    (net (code "63") (name "Net-(Q7-C)") (class "Default")
      (node (ref "Q7") (pin "1") (pinfunction "C_1") (pintype "passive"))
      (node (ref "R47") (pin "1") (pinfunction "1_1") (pintype "passive"))
    )
    (net (code "64") (name "Net-(Q8-B)") (class "Default")
      (node (ref "Q8") (pin "2") (pinfunction "B_2") (pintype "passive"))
      (node (ref "R45") (pin "2") (pinfunction "2_2") (pintype "passive"))
      (node (ref "R46") (pin "2") (pinfunction "2_2") (pintype "passive"))
    )
    (net (code "65") (name "Net-(Q8-C)") (class "Default")
      (node (ref "Q8") (pin "1") (pinfunction "C_1") (pintype "passive"))
      (node (ref "R44") (pin "1") (pinfunction "1_1") (pintype "passive"))
    )
    (net (code "66") (name "Net-(Q9-D)") (class "Default")
      (node (ref "Q9") (pin "2") (pinfunction "D_2") (pintype "passive"))
      (node (ref "R42") (pin "1") (pinfunction "1_1") (pintype "passive"))
    )
    (net (code "67") (name "Net-(Q10-D)") (class "Default")
      (node (ref "Q10") (pin "2") (pinfunction "D_2") (pintype "passive"))
      (node (ref "R43") (pin "1") (pinfunction "1_1") (pintype "passive"))
    )
    (net (code "68") (name "Net-(Rf1-Pad5)") (class "Default")
      (node (ref "Rf1") (pin "5") (pinfunction "5_5") (pintype "passive"))
      (node (ref "U22") (pin "7") (pinfunction "7_7") (pintype "power_in"))
    )
    (net (code "69") (name "Net-(Rf1-Pad6)") (class "Default")
      (node (ref "Rf1") (pin "6") (pinfunction "6_6") (pintype "passive"))
      (node (ref "U22") (pin "5") (pinfunction "5_5") (pintype "power_in"))
    )
    (net (code "70") (name "Net-(Rf1-Pad7)") (class "Default")
      (node (ref "Rf1") (pin "7") (pinfunction "7_7") (pintype "passive"))
      (node (ref "U22") (pin "3") (pinfunction "3_3") (pintype "power_in"))
    )
    (net (code "71") (name "Net-(Rf1-Pad8)") (class "Default")
      (node (ref "Rf1") (pin "8") (pinfunction "8_8") (pintype "passive"))
      (node (ref "U22") (pin "1") (pinfunction "1_1") (pintype "power_in"))
    )
    (net (code "72") (name "Net-(Rf2-Pad5)") (class "Default")
      (node (ref "Rf2") (pin "5") (pinfunction "5_5") (pintype "passive"))
      (node (ref "U23") (pin "7") (pinfunction "7_7") (pintype "power_in"))
    )
    (net (code "73") (name "Net-(Rf2-Pad6)") (class "Default")
      (node (ref "Rf2") (pin "6") (pinfunction "6_6") (pintype "passive"))
      (node (ref "U23") (pin "5") (pinfunction "5_5") (pintype "power_in"))
    )
    (net (code "74") (name "Net-(Rf2-Pad7)") (class "Default")
      (node (ref "Rf2") (pin "7") (pinfunction "7_7") (pintype "passive"))
      (node (ref "U23") (pin "3") (pinfunction "3_3") (pintype "power_in"))
    )
    (net (code "75") (name "Net-(Rf2-Pad8)") (class "Default")
      (node (ref "Rf2") (pin "8") (pinfunction "8_8") (pintype "passive"))
      (node (ref "U23") (pin "1") (pinfunction "1_1") (pintype "power_in"))
    )
    (net (code "76") (name "Net-(U7-VOUT+)") (class "Default")
      (node (ref "F14") (pin "1") (pinfunction "1_1") (pintype "passive"))
      (node (ref "U7") (pin "4") (pinfunction "VOUT+_4") (pintype "power_in"))
    )
    (net (code "77") (name "Net-(U11-IP-)") (class "Default")
      (node (ref "J1") (pin "2") (pinfunction "2_2") (pintype "passive"))
      (node (ref "U11") (pin "5") (pinfunction "IP-_5") (pintype "passive"))
    )
    (net (code "78") (name "Net-(U11-VIOUT)") (class "Default")
      (node (ref "R30") (pin "1") (pinfunction "1_1") (pintype "passive"))
      (node (ref "U11") (pin "3") (pinfunction "VIOUT_3") (pintype "passive"))
    )
    (net (code "79") (name "Net-(U12-IP-)") (class "Default")
      (node (ref "J2") (pin "2") (pinfunction "2_2") (pintype "passive"))
      (node (ref "U12") (pin "5") (pinfunction "IP-_5") (pintype "passive"))
    )
    (net (code "80") (name "Net-(U12-VIOUT)") (class "Default")
      (node (ref "R31") (pin "1") (pinfunction "1_1") (pintype "passive"))
      (node (ref "U12") (pin "3") (pinfunction "VIOUT_3") (pintype "passive"))
    )
    (net (code "81") (name "Net-(U13-IP-)") (class "Default")
      (node (ref "J3") (pin "2") (pinfunction "2_2") (pintype "passive"))
      (node (ref "U13") (pin "5") (pinfunction "IP-_5") (pintype "passive"))
    )
    (net (code "82") (name "Net-(U13-VIOUT)") (class "Default")
      (node (ref "R32") (pin "1") (pinfunction "1_1") (pintype "passive"))
      (node (ref "U13") (pin "3") (pinfunction "VIOUT_3") (pintype "passive"))
    )
    (net (code "83") (name "Net-(U14-IP-)") (class "Default")
      (node (ref "J4") (pin "2") (pinfunction "2_2") (pintype "passive"))
      (node (ref "U14") (pin "5") (pinfunction "IP-_5") (pintype "passive"))
    )
    (net (code "84") (name "Net-(U14-VIOUT)") (class "Default")
      (node (ref "R33") (pin "1") (pinfunction "1_1") (pintype "passive"))
      (node (ref "U14") (pin "3") (pinfunction "VIOUT_3") (pintype "passive"))
    )
    (net (code "85") (name "Net-(U15A-IN1+)") (class "Default")
      (node (ref "C42") (pin "1") (pinfunction "1_1") (pintype "passive"))
      (node (ref "R30") (pin "2") (pinfunction "2_2") (pintype "passive"))
      (node (ref "U15") (pin "3") (pinfunction "IN1+_3") (pintype "input"))
    )
    (net (code "86") (name "Net-(U15A-IN1-)") (class "Default")
      (node (ref "P45") (pin "6") (pinfunction "6_6") (pintype "passive"))
      (node (ref "U15") (pin "1") (pinfunction "OUT1_1") (pintype "output"))
      (node (ref "U15") (pin "2") (pinfunction "IN1-_2") (pintype "input"))
    )
    (net (code "87") (name "Net-(U15B-IN2+)") (class "Default")
      (node (ref "C44") (pin "1") (pinfunction "1_1") (pintype "passive"))
      (node (ref "R31") (pin "2") (pinfunction "2_2") (pintype "passive"))
      (node (ref "U15") (pin "5") (pinfunction "IN2+_5") (pintype "input"))
    )
    (net (code "88") (name "Net-(U15B-IN2-)") (class "Default")
      (node (ref "P45") (pin "5") (pinfunction "5_5") (pintype "passive"))
      (node (ref "U15") (pin "6") (pinfunction "IN2-_6") (pintype "input"))
      (node (ref "U15") (pin "7") (pinfunction "OUT2_7") (pintype "output"))
    )
    (net (code "89") (name "Net-(U15C-IN3+)") (class "Default")
      (node (ref "C46") (pin "1") (pinfunction "1_1") (pintype "passive"))
      (node (ref "R32") (pin "2") (pinfunction "2_2") (pintype "passive"))
      (node (ref "U15") (pin "10") (pinfunction "IN3+_10") (pintype "input"))
    )
    (net (code "90") (name "Net-(U15C-IN3-)") (class "Default")
      (node (ref "P45") (pin "4") (pinfunction "4_4") (pintype "passive"))
      (node (ref "U15") (pin "8") (pinfunction "OUT3_8") (pintype "output"))
      (node (ref "U15") (pin "9") (pinfunction "IN3-_9") (pintype "input"))
    )
    (net (code "91") (name "Net-(U15D-IN4+)") (class "Default")
      (node (ref "C48") (pin "1") (pinfunction "1_1") (pintype "passive"))
      (node (ref "R33") (pin "2") (pinfunction "2_2") (pintype "passive"))
      (node (ref "U15") (pin "12") (pinfunction "IN4+_12") (pintype "input"))
    )
    (net (code "92") (name "Net-(U15D-IN4-)") (class "Default")
      (node (ref "P45") (pin "3") (pinfunction "3_3") (pintype "passive"))
      (node (ref "U15") (pin "13") (pinfunction "IN4-_13") (pintype "input"))
      (node (ref "U15") (pin "14") (pinfunction "OUT4_14") (pintype "output"))
    )
    (net (code "93") (name "POW5V") (class "Default")
      (node (ref "C54") (pin "2") (pinfunction "2_2") (pintype "passive"))
      (node (ref "IO1") (pin "5") (pinfunction "5_5") (pintype "passive"))
      (node (ref "IO1") (pin "6") (pinfunction "6_6") (pintype "passive"))
      (node (ref "IO1") (pin "7") (pinfunction "7_7") (pintype "passive"))
      (node (ref "IO1") (pin "8") (pinfunction "8_8") (pintype "passive"))
      (node (ref "IO2") (pin "3") (pinfunction "3_3") (pintype "passive"))
      (node (ref "IO2") (pin "4") (pinfunction "4_4") (pintype "passive"))
      (node (ref "J5") (pin "2") (pinfunction "2_2") (pintype "passive"))
      (node (ref "R38") (pin "1") (pinfunction "1_1") (pintype "passive"))
      (node (ref "Rf3") (pin "5") (pinfunction "5_5") (pintype "passive"))
      (node (ref "Rf3") (pin "6") (pinfunction "6_6") (pintype "passive"))
      (node (ref "Rf3") (pin "7") (pinfunction "7_7") (pintype "passive"))
      (node (ref "Rf3") (pin "8") (pinfunction "8_8") (pintype "passive"))
      (node (ref "Rf4") (pin "5") (pinfunction "5_5") (pintype "passive"))
      (node (ref "Rf4") (pin "6") (pinfunction "6_6") (pintype "passive"))
      (node (ref "Rf4") (pin "7") (pinfunction "7_7") (pintype "passive"))
      (node (ref "Rf4") (pin "8") (pinfunction "8_8") (pintype "passive"))
      (node (ref "Signal_Out1") (pin "10") (pinfunction "10_10") (pintype "passive"))
      (node (ref "Signal_Out1") (pin "11") (pinfunction "11_11") (pintype "passive"))
      (node (ref "Signal_Out1") (pin "12") (pinfunction "12_12") (pintype "passive"))
      (node (ref "Signal_Out1") (pin "13") (pinfunction "13_13") (pintype "passive"))
      (node (ref "Signal_Out1") (pin "14") (pinfunction "14_14") (pintype "passive"))
      (node (ref "Signal_Out1") (pin "15") (pinfunction "15_15") (pintype "passive"))
      (node (ref "Signal_Out1") (pin "16") (pinfunction "16_16") (pintype "passive"))
      (node (ref "Signal_Out1") (pin "9") (pinfunction "9_9") (pintype "passive"))
      (node (ref "Signal_Out2") (pin "10") (pinfunction "10_10") (pintype "passive"))
      (node (ref "Signal_Out2") (pin "11") (pinfunction "11_11") (pintype "passive"))
      (node (ref "Signal_Out2") (pin "12") (pinfunction "12_12") (pintype "passive"))
      (node (ref "Signal_Out2") (pin "13") (pinfunction "13_13") (pintype "passive"))
      (node (ref "Signal_Out2") (pin "14") (pinfunction "14_14") (pintype "passive"))
      (node (ref "Signal_Out2") (pin "15") (pinfunction "15_15") (pintype "passive"))
      (node (ref "Signal_Out2") (pin "16") (pinfunction "16_16") (pintype "passive"))
      (node (ref "Signal_Out2") (pin "9") (pinfunction "9_9") (pintype "passive"))
      (node (ref "U18") (pin "8") (pinfunction "VDD2_8") (pintype "power_in"))
      (node (ref "U19") (pin "8") (pinfunction "VDD2_8") (pintype "power_in"))
      (node (ref "U20") (pin "8") (pinfunction "VDD2_8") (pintype "power_in"))
      (node (ref "U21") (pin "8") (pinfunction "VDD2_8") (pintype "power_in"))
    )
    (net (code "94") (name "VCC3.3") (class "Default")
      (node (ref "R1") (pin "1") (pinfunction "1_1") (pintype "passive"))
      (node (ref "R2") (pin "1") (pinfunction "1_1") (pintype "passive"))
    )
    (net (code "95") (name "VCC3.3V") (class "Default")
      (node (ref "D8") (pin "2") (pinfunction "K_2") (pintype "passive"))
      (node (ref "F15") (pin "2") (pinfunction "2_2") (pintype "passive"))
      (node (ref "P40") (pin "1") (pinfunction "1_1") (pintype "passive"))
      (node (ref "P41") (pin "1") (pinfunction "1_1") (pintype "passive"))
      (node (ref "P42") (pin "1") (pinfunction "1_1") (pintype "passive"))
      (node (ref "P43") (pin "1") (pinfunction "1_1") (pintype "passive"))
      (node (ref "R37") (pin "1") (pinfunction "1_1") (pintype "passive"))
      (node (ref "Rf1") (pin "1") (pinfunction "1_1") (pintype "passive"))
      (node (ref "Rf1") (pin "2") (pinfunction "2_2") (pintype "passive"))
      (node (ref "Rf1") (pin "3") (pinfunction "3_3") (pintype "passive"))
      (node (ref "Rf1") (pin "4") (pinfunction "4_4") (pintype "passive"))
      (node (ref "Rf2") (pin "1") (pinfunction "1_1") (pintype "passive"))
      (node (ref "Rf2") (pin "2") (pinfunction "2_2") (pintype "passive"))
      (node (ref "Rf2") (pin "3") (pinfunction "3_3") (pintype "passive"))
      (node (ref "Rf2") (pin "4") (pinfunction "4_4") (pintype "passive"))
      (node (ref "U1") (pin "1") (pinfunction "VDD1_1") (pintype "power_in"))
      (node (ref "U18") (pin "1") (pinfunction "VDD1_1") (pintype "power_in"))
      (node (ref "U19") (pin "1") (pinfunction "VDD1_1") (pintype "power_in"))
      (node (ref "U20") (pin "1") (pinfunction "VDD1_1") (pintype "power_in"))
      (node (ref "U21") (pin "1") (pinfunction "VDD1_1") (pintype "power_in"))
    )
    (net (code "96") (name "VCC5") (class "Default")
      (node (ref "R3") (pin "2") (pinfunction "2_2") (pintype "passive"))
      (node (ref "R4") (pin "2") (pinfunction "2_2") (pintype "passive"))
    )
    (net (code "97") (name "VCC5V") (class "Default")
      (node (ref "C43") (pin "2") (pinfunction "2_2") (pintype "passive"))
      (node (ref "C45") (pin "2") (pinfunction "2_2") (pintype "passive"))
      (node (ref "C47") (pin "2") (pinfunction "2_2") (pintype "passive"))
      (node (ref "C49") (pin "2") (pinfunction "2_2") (pintype "passive"))
      (node (ref "C50") (pin "1") (pinfunction "1_1") (pintype "passive"))
      (node (ref "C51") (pin "2") (pinfunction "2_2") (pintype "passive"))
      (node (ref "C56") (pin "2") (pinfunction "2_2") (pintype "passive"))
      (node (ref "F14") (pin "2") (pinfunction "2_2") (pintype "passive"))
      (node (ref "P44") (pin "2") (pinfunction "2_2") (pintype "passive"))
      (node (ref "P44") (pin "3") (pinfunction "3_3") (pintype "passive"))
      (node (ref "P44") (pin "4") (pinfunction "4_4") (pintype "passive"))
      (node (ref "U1") (pin "8") (pinfunction "VDD2_8") (pintype "power_in"))
      (node (ref "U11") (pin "1") (pinfunction "VCC_1") (pintype "passive"))
      (node (ref "U12") (pin "1") (pinfunction "VCC_1") (pintype "passive"))
      (node (ref "U13") (pin "1") (pinfunction "VCC_1") (pintype "passive"))
      (node (ref "U14") (pin "1") (pinfunction "VCC_1") (pintype "passive"))
      (node (ref "U15") (pin "4") (pinfunction "VCC_4") (pintype "power_in"))
      (node (ref "U9") (pin "3") (pinfunction "IN_3") (pintype "passive"))
    )
    (net (code "98") (name "unconnected-(P45-Pad1)") (class "Default")
      (node (ref "P45") (pin "1") (pinfunction "1_1") (pintype "passive+no_connect"))
    )
    (net (code "99") (name "unconnected-(P45-Pad2)") (class "Default")
      (node (ref "P45") (pin "2") (pinfunction "2_2") (pintype "passive+no_connect"))
    )
  )
)
